# Lab-3NANDx8.net
KiCad netlist of a schematic drawn in EAGLE
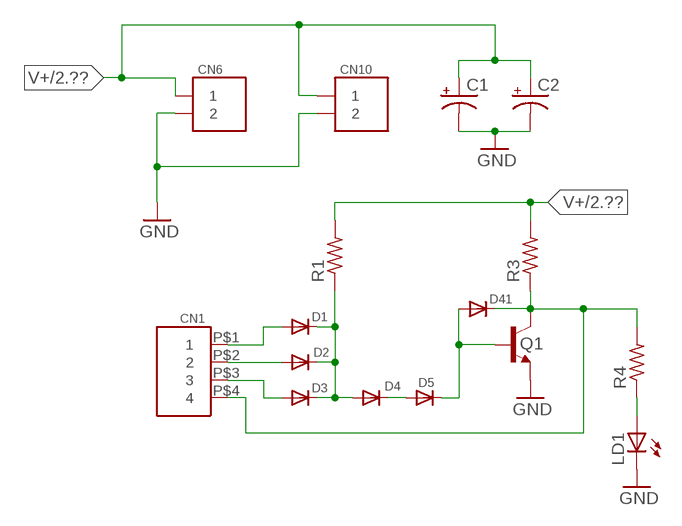
[diagram p0: schematic, sheet 1]
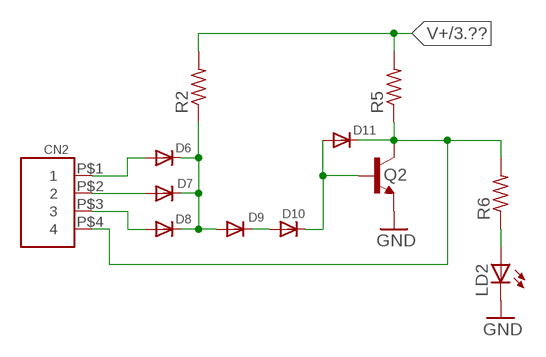
[diagram p1: schematic, sheet 2]
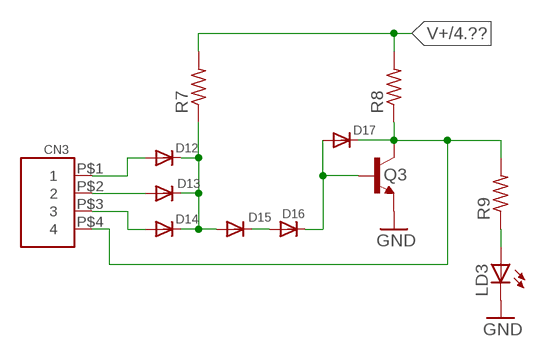
[diagram p2: schematic, sheet 3]
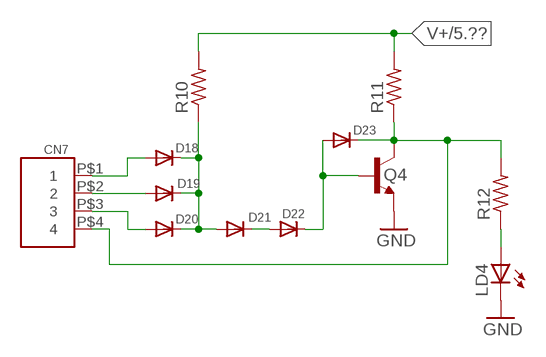
[diagram p3: schematic, sheet 4]
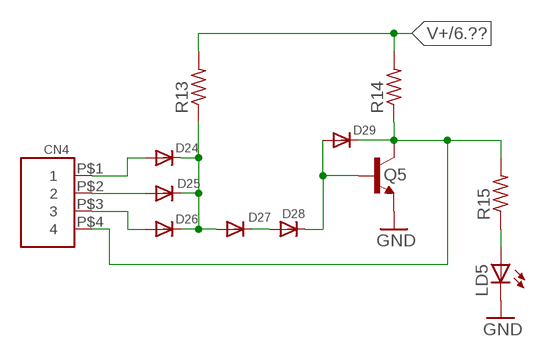
[diagram p4: schematic, sheet 5]
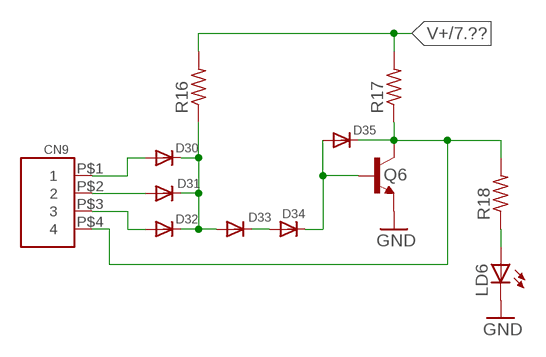
[diagram p5: schematic, sheet 6]
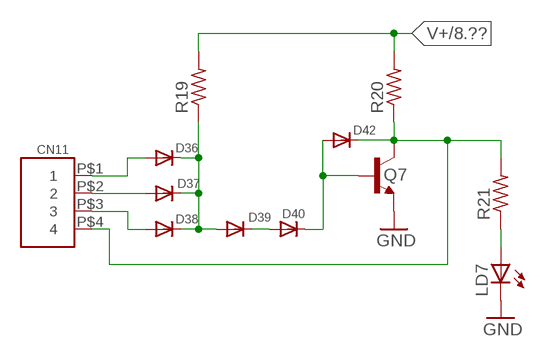
[diagram p6: schematic, sheet 7]
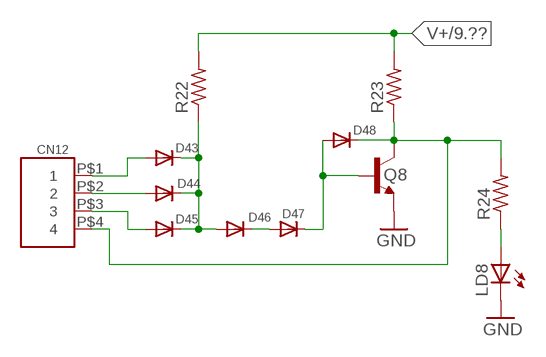
[diagram p7: schematic, sheet 8]
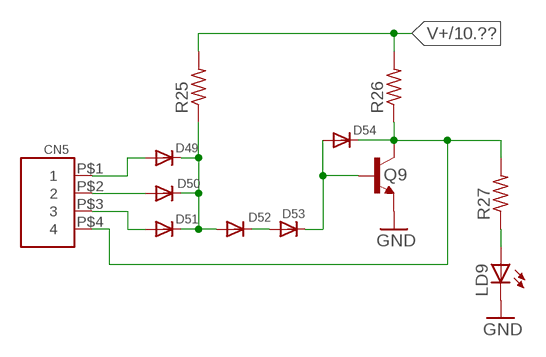
[diagram p8: schematic, sheet 9]
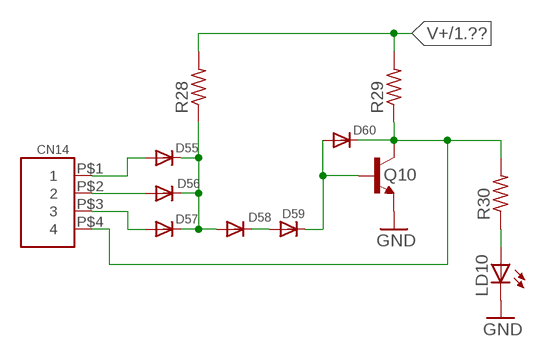
[diagram p9: schematic, sheet 10]

(export (version "E")
  (design (tool "Eeschema 10.0.6"))
  (components
    (comp (ref "CN5")
      (value "HD4")
      (footprint "eagle-import:HD4")
      (libsource (lib "eagle-import") (part "HD4"))
    )
    (comp (ref "D49")
      (value "DIODE-6.3")
      (footprint "eagle-import:DO35-6.3")
      (libsource (lib "eagle-import") (part "DIODE-6.3"))
    )
    (comp (ref "D50")
      (value "DIODE-6.3")
      (footprint "eagle-import:DO35-6.3")
      (libsource (lib "eagle-import") (part "DIODE-6.3"))
    )
    (comp (ref "D51")
      (value "DIODE-6.3")
      (footprint "eagle-import:DO35-6.3")
      (libsource (lib "eagle-import") (part "DIODE-6.3"))
    )
    (comp (ref "D52")
      (value "DIODE-6.3")
      (footprint "eagle-import:DO35-6.3")
      (libsource (lib "eagle-import") (part "DIODE-6.3"))
    )
    (comp (ref "D53")
      (value "DIODE-6.3")
      (footprint "eagle-import:DO35-6.3")
      (libsource (lib "eagle-import") (part "DIODE-6.3"))
    )
    (comp (ref "D54")
      (value "DIODE-7.6")
      (footprint "eagle-import:DO35-7.6")
      (libsource (lib "eagle-import") (part "DIODE-7.6"))
    )
    (comp (ref "LD9")
      (value "LED3MM")
      (footprint "eagle-import:3MM")
      (libsource (lib "eagle-import") (part "LED3MM"))
    )
    (comp (ref "Q9")
      (value "2N3904-1")
      (footprint "eagle-import:TO92BH")
      (libsource (lib "eagle-import") (part "2N3904-1"))
    )
    (comp (ref "R25")
      (value "R1/8-7.6MM")
      (footprint "eagle-import:R0125-7.6")
      (libsource (lib "eagle-import") (part "R1/8-7.6MM"))
    )
    (comp (ref "R26")
      (value "R1/8-7.6MM")
      (footprint "eagle-import:R0125-7.6")
      (libsource (lib "eagle-import") (part "R1/8-7.6MM"))
    )
    (comp (ref "R27")
      (value "R1/8-7.6MM")
      (footprint "eagle-import:R0125-7.6")
      (libsource (lib "eagle-import") (part "R1/8-7.6MM"))
    )
    (comp (ref "CN3")
      (value "HD4")
      (footprint "eagle-import:HD4")
      (libsource (lib "eagle-import") (part "HD4"))
    )
    (comp (ref "D12")
      (value "DIODE-6.3")
      (footprint "eagle-import:DO35-6.3")
      (libsource (lib "eagle-import") (part "DIODE-6.3"))
    )
    (comp (ref "D13")
      (value "DIODE-6.3")
      (footprint "eagle-import:DO35-6.3")
      (libsource (lib "eagle-import") (part "DIODE-6.3"))
    )
    (comp (ref "D14")
      (value "DIODE-6.3")
      (footprint "eagle-import:DO35-6.3")
      (libsource (lib "eagle-import") (part "DIODE-6.3"))
    )
    (comp (ref "D15")
      (value "DIODE-6.3")
      (footprint "eagle-import:DO35-6.3")
      (libsource (lib "eagle-import") (part "DIODE-6.3"))
    )
    (comp (ref "D16")
      (value "DIODE-6.3")
      (footprint "eagle-import:DO35-6.3")
      (libsource (lib "eagle-import") (part "DIODE-6.3"))
    )
    (comp (ref "D17")
      (value "DIODE-7.6")
      (footprint "eagle-import:DO35-7.6")
      (libsource (lib "eagle-import") (part "DIODE-7.6"))
    )
    (comp (ref "LD3")
      (value "LED3MM")
      (footprint "eagle-import:3MM")
      (libsource (lib "eagle-import") (part "LED3MM"))
    )
    (comp (ref "Q3")
      (value "2N3904-1")
      (footprint "eagle-import:TO92BH")
      (libsource (lib "eagle-import") (part "2N3904-1"))
    )
    (comp (ref "R7")
      (value "R1/8-7.6MM")
      (footprint "eagle-import:R0125-7.6")
      (libsource (lib "eagle-import") (part "R1/8-7.6MM"))
    )
    (comp (ref "R8")
      (value "R1/8-7.6MM")
      (footprint "eagle-import:R0125-7.6")
      (libsource (lib "eagle-import") (part "R1/8-7.6MM"))
    )
    (comp (ref "R9")
      (value "R1/8-7.6MM")
      (footprint "eagle-import:R0125-7.6")
      (libsource (lib "eagle-import") (part "R1/8-7.6MM"))
    )
    (comp (ref "C1")
      (value "CPOL-USE2.5-5")
      (footprint "eagle-import:E2,5-5")
      (libsource (lib "eagle-import") (part "CPOL-USE2.5-5"))
    )
    (comp (ref "C2")
      (value "CPOL-USE2.5-5")
      (footprint "eagle-import:E2,5-5")
      (libsource (lib "eagle-import") (part "CPOL-USE2.5-5"))
    )
    (comp (ref "CN1")
      (value "HD4")
      (footprint "eagle-import:HD4")
      (libsource (lib "eagle-import") (part "HD4"))
    )
    (comp (ref "CN6")
      (value "HD2")
      (footprint "eagle-import:HD2")
      (libsource (lib "eagle-import") (part "HD2"))
    )
    (comp (ref "CN10")
      (value "HD2")
      (footprint "eagle-import:HD2")
      (libsource (lib "eagle-import") (part "HD2"))
    )
    (comp (ref "D1")
      (value "DIODE-6.3")
      (footprint "eagle-import:DO35-6.3")
      (libsource (lib "eagle-import") (part "DIODE-6.3"))
    )
    (comp (ref "D2")
      (value "DIODE-6.3")
      (footprint "eagle-import:DO35-6.3")
      (libsource (lib "eagle-import") (part "DIODE-6.3"))
    )
    (comp (ref "D3")
      (value "DIODE-6.3")
      (footprint "eagle-import:DO35-6.3")
      (libsource (lib "eagle-import") (part "DIODE-6.3"))
    )
    (comp (ref "D4")
      (value "DIODE-6.3")
      (footprint "eagle-import:DO35-6.3")
      (libsource (lib "eagle-import") (part "DIODE-6.3"))
    )
    (comp (ref "D5")
      (value "DIODE-6.3")
      (footprint "eagle-import:DO35-6.3")
      (libsource (lib "eagle-import") (part "DIODE-6.3"))
    )
    (comp (ref "D41")
      (value "DIODE-7.6")
      (footprint "eagle-import:DO35-7.6")
      (libsource (lib "eagle-import") (part "DIODE-7.6"))
    )
    (comp (ref "LD1")
      (value "LED3MM")
      (footprint "eagle-import:3MM")
      (libsource (lib "eagle-import") (part "LED3MM"))
    )
    (comp (ref "Q1")
      (value "2N3904-1")
      (footprint "eagle-import:TO92BH")
      (libsource (lib "eagle-import") (part "2N3904-1"))
    )
    (comp (ref "R1")
      (value "R1/8-7.6MM")
      (footprint "eagle-import:R0125-7.6")
      (libsource (lib "eagle-import") (part "R1/8-7.6MM"))
    )
    (comp (ref "R3")
      (value "R1/8-7.6MM")
      (footprint "eagle-import:R0125-7.6")
      (libsource (lib "eagle-import") (part "R1/8-7.6MM"))
    )
    (comp (ref "R4")
      (value "R1/8-7.6MM")
      (footprint "eagle-import:R0125-7.6")
      (libsource (lib "eagle-import") (part "R1/8-7.6MM"))
    )
    (comp (ref "CN7")
      (value "HD4")
      (footprint "eagle-import:HD4")
      (libsource (lib "eagle-import") (part "HD4"))
    )
    (comp (ref "D18")
      (value "DIODE-6.3")
      (footprint "eagle-import:DO35-6.3")
      (libsource (lib "eagle-import") (part "DIODE-6.3"))
    )
    (comp (ref "D19")
      (value "DIODE-6.3")
      (footprint "eagle-import:DO35-6.3")
      (libsource (lib "eagle-import") (part "DIODE-6.3"))
    )
    (comp (ref "D20")
      (value "DIODE-6.3")
      (footprint "eagle-import:DO35-6.3")
      (libsource (lib "eagle-import") (part "DIODE-6.3"))
    )
    (comp (ref "D21")
      (value "DIODE-6.3")
      (footprint "eagle-import:DO35-6.3")
      (libsource (lib "eagle-import") (part "DIODE-6.3"))
    )
    (comp (ref "D22")
      (value "DIODE-6.3")
      (footprint "eagle-import:DO35-6.3")
      (libsource (lib "eagle-import") (part "DIODE-6.3"))
    )
    (comp (ref "D23")
      (value "DIODE-7.6")
      (footprint "eagle-import:DO35-7.6")
      (libsource (lib "eagle-import") (part "DIODE-7.6"))
    )
    (comp (ref "LD4")
      (value "LED3MM")
      (footprint "eagle-import:3MM")
      (libsource (lib "eagle-import") (part "LED3MM"))
    )
    (comp (ref "Q4")
      (value "2N3904-1")
      (footprint "eagle-import:TO92BH")
      (libsource (lib "eagle-import") (part "2N3904-1"))
    )
    (comp (ref "R10")
      (value "R1/8-7.6MM")
      (footprint "eagle-import:R0125-7.6")
      (libsource (lib "eagle-import") (part "R1/8-7.6MM"))
    )
    (comp (ref "R11")
      (value "R1/8-7.6MM")
      (footprint "eagle-import:R0125-7.6")
      (libsource (lib "eagle-import") (part "R1/8-7.6MM"))
    )
    (comp (ref "R12")
      (value "R1/8-7.6MM")
      (footprint "eagle-import:R0125-7.6")
      (libsource (lib "eagle-import") (part "R1/8-7.6MM"))
    )
    (comp (ref "CN2")
      (value "HD4")
      (footprint "eagle-import:HD4")
      (libsource (lib "eagle-import") (part "HD4"))
    )
    (comp (ref "D6")
      (value "DIODE-6.3")
      (footprint "eagle-import:DO35-6.3")
      (libsource (lib "eagle-import") (part "DIODE-6.3"))
    )
    (comp (ref "D7")
      (value "DIODE-6.3")
      (footprint "eagle-import:DO35-6.3")
      (libsource (lib "eagle-import") (part "DIODE-6.3"))
    )
    (comp (ref "D8")
      (value "DIODE-6.3")
      (footprint "eagle-import:DO35-6.3")
      (libsource (lib "eagle-import") (part "DIODE-6.3"))
    )
    (comp (ref "D9")
      (value "DIODE-6.3")
      (footprint "eagle-import:DO35-6.3")
      (libsource (lib "eagle-import") (part "DIODE-6.3"))
    )
    (comp (ref "D10")
      (value "DIODE-6.3")
      (footprint "eagle-import:DO35-6.3")
      (libsource (lib "eagle-import") (part "DIODE-6.3"))
    )
    (comp (ref "D11")
      (value "DIODE-7.6")
      (footprint "eagle-import:DO35-7.6")
      (libsource (lib "eagle-import") (part "DIODE-7.6"))
    )
    (comp (ref "LD2")
      (value "LED3MM")
      (footprint "eagle-import:3MM")
      (libsource (lib "eagle-import") (part "LED3MM"))
    )
    (comp (ref "Q2")
      (value "2N3904-1")
      (footprint "eagle-import:TO92BH")
      (libsource (lib "eagle-import") (part "2N3904-1"))
    )
    (comp (ref "R2")
      (value "R1/8-7.6MM")
      (footprint "eagle-import:R0125-7.6")
      (libsource (lib "eagle-import") (part "R1/8-7.6MM"))
    )
    (comp (ref "R5")
      (value "R1/8-7.6MM")
      (footprint "eagle-import:R0125-7.6")
      (libsource (lib "eagle-import") (part "R1/8-7.6MM"))
    )
    (comp (ref "R6")
      (value "R1/8-7.6MM")
      (footprint "eagle-import:R0125-7.6")
      (libsource (lib "eagle-import") (part "R1/8-7.6MM"))
    )
    (comp (ref "CN9")
      (value "HD4")
      (footprint "eagle-import:HD4")
      (libsource (lib "eagle-import") (part "HD4"))
    )
    (comp (ref "D30")
      (value "DIODE-6.3")
      (footprint "eagle-import:DO35-6.3")
      (libsource (lib "eagle-import") (part "DIODE-6.3"))
    )
    (comp (ref "D31")
      (value "DIODE-6.3")
      (footprint "eagle-import:DO35-6.3")
      (libsource (lib "eagle-import") (part "DIODE-6.3"))
    )
    (comp (ref "D32")
      (value "DIODE-6.3")
      (footprint "eagle-import:DO35-6.3")
      (libsource (lib "eagle-import") (part "DIODE-6.3"))
    )
    (comp (ref "D33")
      (value "DIODE-6.3")
      (footprint "eagle-import:DO35-6.3")
      (libsource (lib "eagle-import") (part "DIODE-6.3"))
    )
    (comp (ref "D34")
      (value "DIODE-6.3")
      (footprint "eagle-import:DO35-6.3")
      (libsource (lib "eagle-import") (part "DIODE-6.3"))
    )
    (comp (ref "D35")
      (value "DIODE-7.6")
      (footprint "eagle-import:DO35-7.6")
      (libsource (lib "eagle-import") (part "DIODE-7.6"))
    )
    (comp (ref "LD6")
      (value "LED3MM")
      (footprint "eagle-import:3MM")
      (libsource (lib "eagle-import") (part "LED3MM"))
    )
    (comp (ref "Q6")
      (value "2N3904-1")
      (footprint "eagle-import:TO92BH")
      (libsource (lib "eagle-import") (part "2N3904-1"))
    )
    (comp (ref "R16")
      (value "R1/8-7.6MM")
      (footprint "eagle-import:R0125-7.6")
      (libsource (lib "eagle-import") (part "R1/8-7.6MM"))
    )
    (comp (ref "R17")
      (value "R1/8-7.6MM")
      (footprint "eagle-import:R0125-7.6")
      (libsource (lib "eagle-import") (part "R1/8-7.6MM"))
    )
    (comp (ref "R18")
      (value "R1/8-7.6MM")
      (footprint "eagle-import:R0125-7.6")
      (libsource (lib "eagle-import") (part "R1/8-7.6MM"))
    )
    (comp (ref "CN4")
      (value "HD4")
      (footprint "eagle-import:HD4")
      (libsource (lib "eagle-import") (part "HD4"))
    )
    (comp (ref "D24")
      (value "DIODE-6.3")
      (footprint "eagle-import:DO35-6.3")
      (libsource (lib "eagle-import") (part "DIODE-6.3"))
    )
    (comp (ref "D25")
      (value "DIODE-6.3")
      (footprint "eagle-import:DO35-6.3")
      (libsource (lib "eagle-import") (part "DIODE-6.3"))
    )
    (comp (ref "D26")
      (value "DIODE-6.3")
      (footprint "eagle-import:DO35-6.3")
      (libsource (lib "eagle-import") (part "DIODE-6.3"))
    )
    (comp (ref "D27")
      (value "DIODE-6.3")
      (footprint "eagle-import:DO35-6.3")
      (libsource (lib "eagle-import") (part "DIODE-6.3"))
    )
    (comp (ref "D28")
      (value "DIODE-6.3")
      (footprint "eagle-import:DO35-6.3")
      (libsource (lib "eagle-import") (part "DIODE-6.3"))
    )
    (comp (ref "D29")
      (value "DIODE-7.6")
      (footprint "eagle-import:DO35-7.6")
      (libsource (lib "eagle-import") (part "DIODE-7.6"))
    )
    (comp (ref "LD5")
      (value "LED3MM")
      (footprint "eagle-import:3MM")
      (libsource (lib "eagle-import") (part "LED3MM"))
    )
    (comp (ref "Q5")
      (value "2N3904-1")
      (footprint "eagle-import:TO92BH")
      (libsource (lib "eagle-import") (part "2N3904-1"))
    )
    (comp (ref "R13")
      (value "R1/8-7.6MM")
      (footprint "eagle-import:R0125-7.6")
      (libsource (lib "eagle-import") (part "R1/8-7.6MM"))
    )
    (comp (ref "R14")
      (value "R1/8-7.6MM")
      (footprint "eagle-import:R0125-7.6")
      (libsource (lib "eagle-import") (part "R1/8-7.6MM"))
    )
    (comp (ref "R15")
      (value "R1/8-7.6MM")
      (footprint "eagle-import:R0125-7.6")
      (libsource (lib "eagle-import") (part "R1/8-7.6MM"))
    )
    (comp (ref "CN12")
      (value "HD4")
      (footprint "eagle-import:HD4")
      (libsource (lib "eagle-import") (part "HD4"))
    )
    (comp (ref "D43")
      (value "DIODE-6.3")
      (footprint "eagle-import:DO35-6.3")
      (libsource (lib "eagle-import") (part "DIODE-6.3"))
    )
    (comp (ref "D44")
      (value "DIODE-6.3")
      (footprint "eagle-import:DO35-6.3")
      (libsource (lib "eagle-import") (part "DIODE-6.3"))
    )
    (comp (ref "D45")
      (value "DIODE-6.3")
      (footprint "eagle-import:DO35-6.3")
      (libsource (lib "eagle-import") (part "DIODE-6.3"))
    )
    (comp (ref "D46")
      (value "DIODE-6.3")
      (footprint "eagle-import:DO35-6.3")
      (libsource (lib "eagle-import") (part "DIODE-6.3"))
    )
    (comp (ref "D47")
      (value "DIODE-6.3")
      (footprint "eagle-import:DO35-6.3")
      (libsource (lib "eagle-import") (part "DIODE-6.3"))
    )
    (comp (ref "D48")
      (value "DIODE-7.6")
      (footprint "eagle-import:DO35-7.6")
      (libsource (lib "eagle-import") (part "DIODE-7.6"))
    )
    (comp (ref "LD8")
      (value "LED3MM")
      (footprint "eagle-import:3MM")
      (libsource (lib "eagle-import") (part "LED3MM"))
    )
    (comp (ref "Q8")
      (value "2N3904-1")
      (footprint "eagle-import:TO92BH")
      (libsource (lib "eagle-import") (part "2N3904-1"))
    )
    (comp (ref "R22")
      (value "R1/8-7.6MM")
      (footprint "eagle-import:R0125-7.6")
      (libsource (lib "eagle-import") (part "R1/8-7.6MM"))
    )
    (comp (ref "R23")
      (value "R1/8-7.6MM")
      (footprint "eagle-import:R0125-7.6")
      (libsource (lib "eagle-import") (part "R1/8-7.6MM"))
    )
    (comp (ref "R24")
      (value "R1/8-7.6MM")
      (footprint "eagle-import:R0125-7.6")
      (libsource (lib "eagle-import") (part "R1/8-7.6MM"))
    )
    (comp (ref "CN11")
      (value "HD4")
      (footprint "eagle-import:HD4")
      (libsource (lib "eagle-import") (part "HD4"))
    )
    (comp (ref "D36")
      (value "DIODE-6.3")
      (footprint "eagle-import:DO35-6.3")
      (libsource (lib "eagle-import") (part "DIODE-6.3"))
    )
    (comp (ref "D37")
      (value "DIODE-6.3")
      (footprint "eagle-import:DO35-6.3")
      (libsource (lib "eagle-import") (part "DIODE-6.3"))
    )
    (comp (ref "D38")
      (value "DIODE-6.3")
      (footprint "eagle-import:DO35-6.3")
      (libsource (lib "eagle-import") (part "DIODE-6.3"))
    )
    (comp (ref "D39")
      (value "DIODE-6.3")
      (footprint "eagle-import:DO35-6.3")
      (libsource (lib "eagle-import") (part "DIODE-6.3"))
    )
    (comp (ref "D40")
      (value "DIODE-6.3")
      (footprint "eagle-import:DO35-6.3")
      (libsource (lib "eagle-import") (part "DIODE-6.3"))
    )
    (comp (ref "D42")
      (value "DIODE-7.6")
      (footprint "eagle-import:DO35-7.6")
      (libsource (lib "eagle-import") (part "DIODE-7.6"))
    )
    (comp (ref "LD7")
      (value "LED3MM")
      (footprint "eagle-import:3MM")
      (libsource (lib "eagle-import") (part "LED3MM"))
    )
    (comp (ref "Q7")
      (value "2N3904-1")
      (footprint "eagle-import:TO92BH")
      (libsource (lib "eagle-import") (part "2N3904-1"))
    )
    (comp (ref "R19")
      (value "R1/8-7.6MM")
      (footprint "eagle-import:R0125-7.6")
      (libsource (lib "eagle-import") (part "R1/8-7.6MM"))
    )
    (comp (ref "R20")
      (value "R1/8-7.6MM")
      (footprint "eagle-import:R0125-7.6")
      (libsource (lib "eagle-import") (part "R1/8-7.6MM"))
    )
    (comp (ref "R21")
      (value "R1/8-7.6MM")
      (footprint "eagle-import:R0125-7.6")
      (libsource (lib "eagle-import") (part "R1/8-7.6MM"))
    )
    (comp (ref "CN14")
      (value "HD4")
      (footprint "eagle-import:HD4")
      (libsource (lib "eagle-import") (part "HD4"))
    )
    (comp (ref "D55")
      (value "DIODE-6.3")
      (footprint "eagle-import:DO35-6.3")
      (libsource (lib "eagle-import") (part "DIODE-6.3"))
    )
    (comp (ref "D56")
      (value "DIODE-6.3")
      (footprint "eagle-import:DO35-6.3")
      (libsource (lib "eagle-import") (part "DIODE-6.3"))
    )
    (comp (ref "D57")
      (value "DIODE-6.3")
      (footprint "eagle-import:DO35-6.3")
      (libsource (lib "eagle-import") (part "DIODE-6.3"))
    )
    (comp (ref "D58")
      (value "DIODE-6.3")
      (footprint "eagle-import:DO35-6.3")
      (libsource (lib "eagle-import") (part "DIODE-6.3"))
    )
    (comp (ref "D59")
      (value "DIODE-6.3")
      (footprint "eagle-import:DO35-6.3")
      (libsource (lib "eagle-import") (part "DIODE-6.3"))
    )
    (comp (ref "D60")
      (value "DIODE-7.6")
      (footprint "eagle-import:DO35-7.6")
      (libsource (lib "eagle-import") (part "DIODE-7.6"))
    )
    (comp (ref "LD10")
      (value "LED3MM")
      (footprint "eagle-import:3MM")
      (libsource (lib "eagle-import") (part "LED3MM"))
    )
    (comp (ref "Q10")
      (value "2N3904-1")
      (footprint "eagle-import:TO92BH")
      (libsource (lib "eagle-import") (part "2N3904-1"))
    )
    (comp (ref "R28")
      (value "R1/8-7.6MM")
      (footprint "eagle-import:R0125-7.6")
      (libsource (lib "eagle-import") (part "R1/8-7.6MM"))
    )
    (comp (ref "R29")
      (value "R1/8-7.6MM")
      (footprint "eagle-import:R0125-7.6")
      (libsource (lib "eagle-import") (part "R1/8-7.6MM"))
    )
    (comp (ref "R30")
      (value "R1/8-7.6MM")
      (footprint "eagle-import:R0125-7.6")
      (libsource (lib "eagle-import") (part "R1/8-7.6MM"))
    )
  )
  (nets
    (net (code "1") (name "GND") (class "Default")
      (node (ref "C1") (pin "-") (pinfunction "-_-") (pintype "passive"))
      (node (ref "C2") (pin "-") (pinfunction "-_-") (pintype "passive"))
      (node (ref "CN10") (pin "P$2") (pinfunction "2_P$2") (pintype "bidirectional"))
      (node (ref "CN6") (pin "P$2") (pinfunction "2_P$2") (pintype "bidirectional"))
      (node (ref "LD1") (pin "C") (pinfunction "C_C") (pintype "bidirectional"))
      (node (ref "LD10") (pin "C") (pinfunction "C_C") (pintype "bidirectional"))
      (node (ref "LD2") (pin "C") (pinfunction "C_C") (pintype "bidirectional"))
      (node (ref "LD3") (pin "C") (pinfunction "C_C") (pintype "bidirectional"))
      (node (ref "LD4") (pin "C") (pinfunction "C_C") (pintype "bidirectional"))
      (node (ref "LD5") (pin "C") (pinfunction "C_C") (pintype "bidirectional"))
      (node (ref "LD6") (pin "C") (pinfunction "C_C") (pintype "bidirectional"))
      (node (ref "LD7") (pin "C") (pinfunction "C_C") (pintype "bidirectional"))
      (node (ref "LD8") (pin "C") (pinfunction "C_C") (pintype "bidirectional"))
      (node (ref "LD9") (pin "C") (pinfunction "C_C") (pintype "bidirectional"))
      (node (ref "Q1") (pin "1") (pinfunction "E_1") (pintype "passive"))
      (node (ref "Q10") (pin "1") (pinfunction "E_1") (pintype "passive"))
      (node (ref "Q2") (pin "1") (pinfunction "E_1") (pintype "passive"))
      (node (ref "Q3") (pin "1") (pinfunction "E_1") (pintype "passive"))
      (node (ref "Q4") (pin "1") (pinfunction "E_1") (pintype "passive"))
      (node (ref "Q5") (pin "1") (pinfunction "E_1") (pintype "passive"))
      (node (ref "Q6") (pin "1") (pinfunction "E_1") (pintype "passive"))
      (node (ref "Q7") (pin "1") (pinfunction "E_1") (pintype "passive"))
      (node (ref "Q8") (pin "1") (pinfunction "E_1") (pintype "passive"))
      (node (ref "Q9") (pin "1") (pinfunction "E_1") (pintype "passive"))
    )
    (net (code "2") (name "Net-(CN1-1)") (class "Default")
      (node (ref "CN1") (pin "P$1") (pinfunction "1_P$1") (pintype "bidirectional"))
      (node (ref "D1") (pin "A") (pinfunction "A_A") (pintype "passive"))
    )
    (net (code "3") (name "Net-(CN1-2)") (class "Default")
      (node (ref "CN1") (pin "P$2") (pinfunction "2_P$2") (pintype "bidirectional"))
      (node (ref "D2") (pin "A") (pinfunction "A_A") (pintype "passive"))
    )
    (net (code "4") (name "Net-(CN1-3)") (class "Default")
      (node (ref "CN1") (pin "P$3") (pinfunction "3_P$3") (pintype "bidirectional"))
      (node (ref "D3") (pin "A") (pinfunction "A_A") (pintype "passive"))
    )
    (net (code "5") (name "Net-(CN1-4)") (class "Default")
      (node (ref "CN1") (pin "P$4") (pinfunction "4_P$4") (pintype "bidirectional"))
      (node (ref "D41") (pin "C") (pinfunction "C_C") (pintype "passive"))
      (node (ref "Q1") (pin "3") (pinfunction "C_3") (pintype "passive"))
      (node (ref "R3") (pin "1") (pinfunction "1_1") (pintype "passive"))
      (node (ref "R4") (pin "2") (pinfunction "2_2") (pintype "passive"))
    )
    (net (code "6") (name "Net-(CN2-1)") (class "Default")
      (node (ref "CN2") (pin "P$1") (pinfunction "1_P$1") (pintype "bidirectional"))
      (node (ref "D6") (pin "A") (pinfunction "A_A") (pintype "passive"))
    )
    (net (code "7") (name "Net-(CN2-2)") (class "Default")
      (node (ref "CN2") (pin "P$2") (pinfunction "2_P$2") (pintype "bidirectional"))
      (node (ref "D7") (pin "A") (pinfunction "A_A") (pintype "passive"))
    )
    (net (code "8") (name "Net-(CN2-3)") (class "Default")
      (node (ref "CN2") (pin "P$3") (pinfunction "3_P$3") (pintype "bidirectional"))
      (node (ref "D8") (pin "A") (pinfunction "A_A") (pintype "passive"))
    )
    (net (code "9") (name "Net-(CN2-4)") (class "Default")
      (node (ref "CN2") (pin "P$4") (pinfunction "4_P$4") (pintype "bidirectional"))
      (node (ref "D11") (pin "C") (pinfunction "C_C") (pintype "passive"))
      (node (ref "Q2") (pin "3") (pinfunction "C_3") (pintype "passive"))
      (node (ref "R5") (pin "1") (pinfunction "1_1") (pintype "passive"))
      (node (ref "R6") (pin "2") (pinfunction "2_2") (pintype "passive"))
    )
    (net (code "10") (name "Net-(CN3-1)") (class "Default")
      (node (ref "CN3") (pin "P$1") (pinfunction "1_P$1") (pintype "bidirectional"))
      (node (ref "D12") (pin "A") (pinfunction "A_A") (pintype "passive"))
    )
    (net (code "11") (name "Net-(CN3-2)") (class "Default")
      (node (ref "CN3") (pin "P$2") (pinfunction "2_P$2") (pintype "bidirectional"))
      (node (ref "D13") (pin "A") (pinfunction "A_A") (pintype "passive"))
    )
    (net (code "12") (name "Net-(CN3-3)") (class "Default")
      (node (ref "CN3") (pin "P$3") (pinfunction "3_P$3") (pintype "bidirectional"))
      (node (ref "D14") (pin "A") (pinfunction "A_A") (pintype "passive"))
    )
    (net (code "13") (name "Net-(CN3-4)") (class "Default")
      (node (ref "CN3") (pin "P$4") (pinfunction "4_P$4") (pintype "bidirectional"))
      (node (ref "D17") (pin "C") (pinfunction "C_C") (pintype "passive"))
      (node (ref "Q3") (pin "3") (pinfunction "C_3") (pintype "passive"))
      (node (ref "R8") (pin "1") (pinfunction "1_1") (pintype "passive"))
      (node (ref "R9") (pin "2") (pinfunction "2_2") (pintype "passive"))
    )
    (net (code "14") (name "Net-(CN4-1)") (class "Default")
      (node (ref "CN4") (pin "P$1") (pinfunction "1_P$1") (pintype "bidirectional"))
      (node (ref "D24") (pin "A") (pinfunction "A_A") (pintype "passive"))
    )
    (net (code "15") (name "Net-(CN4-2)") (class "Default")
      (node (ref "CN4") (pin "P$2") (pinfunction "2_P$2") (pintype "bidirectional"))
      (node (ref "D25") (pin "A") (pinfunction "A_A") (pintype "passive"))
    )
    (net (code "16") (name "Net-(CN4-3)") (class "Default")
      (node (ref "CN4") (pin "P$3") (pinfunction "3_P$3") (pintype "bidirectional"))
      (node (ref "D26") (pin "A") (pinfunction "A_A") (pintype "passive"))
    )
    (net (code "17") (name "Net-(CN4-4)") (class "Default")
      (node (ref "CN4") (pin "P$4") (pinfunction "4_P$4") (pintype "bidirectional"))
      (node (ref "D29") (pin "C") (pinfunction "C_C") (pintype "passive"))
      (node (ref "Q5") (pin "3") (pinfunction "C_3") (pintype "passive"))
      (node (ref "R14") (pin "1") (pinfunction "1_1") (pintype "passive"))
      (node (ref "R15") (pin "2") (pinfunction "2_2") (pintype "passive"))
    )
    (net (code "18") (name "Net-(CN5-1)") (class "Default")
      (node (ref "CN5") (pin "P$1") (pinfunction "1_P$1") (pintype "bidirectional"))
      (node (ref "D49") (pin "A") (pinfunction "A_A") (pintype "passive"))
    )
    (net (code "19") (name "Net-(CN5-2)") (class "Default")
      (node (ref "CN5") (pin "P$2") (pinfunction "2_P$2") (pintype "bidirectional"))
      (node (ref "D50") (pin "A") (pinfunction "A_A") (pintype "passive"))
    )
    (net (code "20") (name "Net-(CN5-3)") (class "Default")
      (node (ref "CN5") (pin "P$3") (pinfunction "3_P$3") (pintype "bidirectional"))
      (node (ref "D51") (pin "A") (pinfunction "A_A") (pintype "passive"))
    )
    (net (code "21") (name "Net-(CN5-4)") (class "Default")
      (node (ref "CN5") (pin "P$4") (pinfunction "4_P$4") (pintype "bidirectional"))
      (node (ref "D54") (pin "C") (pinfunction "C_C") (pintype "passive"))
      (node (ref "Q9") (pin "3") (pinfunction "C_3") (pintype "passive"))
      (node (ref "R26") (pin "1") (pinfunction "1_1") (pintype "passive"))
      (node (ref "R27") (pin "2") (pinfunction "2_2") (pintype "passive"))
    )
    (net (code "22") (name "Net-(CN7-1)") (class "Default")
      (node (ref "CN7") (pin "P$1") (pinfunction "1_P$1") (pintype "bidirectional"))
      (node (ref "D18") (pin "A") (pinfunction "A_A") (pintype "passive"))
    )
    (net (code "23") (name "Net-(CN7-2)") (class "Default")
      (node (ref "CN7") (pin "P$2") (pinfunction "2_P$2") (pintype "bidirectional"))
      (node (ref "D19") (pin "A") (pinfunction "A_A") (pintype "passive"))
    )
    (net (code "24") (name "Net-(CN7-3)") (class "Default")
      (node (ref "CN7") (pin "P$3") (pinfunction "3_P$3") (pintype "bidirectional"))
      (node (ref "D20") (pin "A") (pinfunction "A_A") (pintype "passive"))
    )
    (net (code "25") (name "Net-(CN7-4)") (class "Default")
      (node (ref "CN7") (pin "P$4") (pinfunction "4_P$4") (pintype "bidirectional"))
      (node (ref "D23") (pin "C") (pinfunction "C_C") (pintype "passive"))
      (node (ref "Q4") (pin "3") (pinfunction "C_3") (pintype "passive"))
      (node (ref "R11") (pin "1") (pinfunction "1_1") (pintype "passive"))
      (node (ref "R12") (pin "2") (pinfunction "2_2") (pintype "passive"))
    )
    (net (code "26") (name "Net-(CN9-1)") (class "Default")
      (node (ref "CN9") (pin "P$1") (pinfunction "1_P$1") (pintype "bidirectional"))
      (node (ref "D30") (pin "A") (pinfunction "A_A") (pintype "passive"))
    )
    (net (code "27") (name "Net-(CN9-2)") (class "Default")
      (node (ref "CN9") (pin "P$2") (pinfunction "2_P$2") (pintype "bidirectional"))
      (node (ref "D31") (pin "A") (pinfunction "A_A") (pintype "passive"))
    )
    (net (code "28") (name "Net-(CN9-3)") (class "Default")
      (node (ref "CN9") (pin "P$3") (pinfunction "3_P$3") (pintype "bidirectional"))
      (node (ref "D32") (pin "A") (pinfunction "A_A") (pintype "passive"))
    )
    (net (code "29") (name "Net-(CN9-4)") (class "Default")
      (node (ref "CN9") (pin "P$4") (pinfunction "4_P$4") (pintype "bidirectional"))
      (node (ref "D35") (pin "C") (pinfunction "C_C") (pintype "passive"))
      (node (ref "Q6") (pin "3") (pinfunction "C_3") (pintype "passive"))
      (node (ref "R17") (pin "1") (pinfunction "1_1") (pintype "passive"))
      (node (ref "R18") (pin "2") (pinfunction "2_2") (pintype "passive"))
    )
    (net (code "30") (name "Net-(CN11-1)") (class "Default")
      (node (ref "CN11") (pin "P$1") (pinfunction "1_P$1") (pintype "bidirectional"))
      (node (ref "D36") (pin "A") (pinfunction "A_A") (pintype "passive"))
    )
    (net (code "31") (name "Net-(CN11-2)") (class "Default")
      (node (ref "CN11") (pin "P$2") (pinfunction "2_P$2") (pintype "bidirectional"))
      (node (ref "D37") (pin "A") (pinfunction "A_A") (pintype "passive"))
    )
    (net (code "32") (name "Net-(CN11-3)") (class "Default")
      (node (ref "CN11") (pin "P$3") (pinfunction "3_P$3") (pintype "bidirectional"))
      (node (ref "D38") (pin "A") (pinfunction "A_A") (pintype "passive"))
    )
    (net (code "33") (name "Net-(CN11-4)") (class "Default")
      (node (ref "CN11") (pin "P$4") (pinfunction "4_P$4") (pintype "bidirectional"))
      (node (ref "D42") (pin "C") (pinfunction "C_C") (pintype "passive"))
      (node (ref "Q7") (pin "3") (pinfunction "C_3") (pintype "passive"))
      (node (ref "R20") (pin "1") (pinfunction "1_1") (pintype "passive"))
      (node (ref "R21") (pin "2") (pinfunction "2_2") (pintype "passive"))
    )
    (net (code "34") (name "Net-(CN12-1)") (class "Default")
      (node (ref "CN12") (pin "P$1") (pinfunction "1_P$1") (pintype "bidirectional"))
      (node (ref "D43") (pin "A") (pinfunction "A_A") (pintype "passive"))
    )
    (net (code "35") (name "Net-(CN12-2)") (class "Default")
      (node (ref "CN12") (pin "P$2") (pinfunction "2_P$2") (pintype "bidirectional"))
      (node (ref "D44") (pin "A") (pinfunction "A_A") (pintype "passive"))
    )
    (net (code "36") (name "Net-(CN12-3)") (class "Default")
      (node (ref "CN12") (pin "P$3") (pinfunction "3_P$3") (pintype "bidirectional"))
      (node (ref "D45") (pin "A") (pinfunction "A_A") (pintype "passive"))
    )
    (net (code "37") (name "Net-(CN12-4)") (class "Default")
      (node (ref "CN12") (pin "P$4") (pinfunction "4_P$4") (pintype "bidirectional"))
      (node (ref "D48") (pin "C") (pinfunction "C_C") (pintype "passive"))
      (node (ref "Q8") (pin "3") (pinfunction "C_3") (pintype "passive"))
      (node (ref "R23") (pin "1") (pinfunction "1_1") (pintype "passive"))
      (node (ref "R24") (pin "2") (pinfunction "2_2") (pintype "passive"))
    )
    (net (code "38") (name "Net-(CN14-1)") (class "Default")
      (node (ref "CN14") (pin "P$1") (pinfunction "1_P$1") (pintype "bidirectional"))
      (node (ref "D55") (pin "A") (pinfunction "A_A") (pintype "passive"))
    )
    (net (code "39") (name "Net-(CN14-2)") (class "Default")
      (node (ref "CN14") (pin "P$2") (pinfunction "2_P$2") (pintype "bidirectional"))
      (node (ref "D56") (pin "A") (pinfunction "A_A") (pintype "passive"))
    )
    (net (code "40") (name "Net-(CN14-3)") (class "Default")
      (node (ref "CN14") (pin "P$3") (pinfunction "3_P$3") (pintype "bidirectional"))
      (node (ref "D57") (pin "A") (pinfunction "A_A") (pintype "passive"))
    )
    (net (code "41") (name "Net-(CN14-4)") (class "Default")
      (node (ref "CN14") (pin "P$4") (pinfunction "4_P$4") (pintype "bidirectional"))
      (node (ref "D60") (pin "C") (pinfunction "C_C") (pintype "passive"))
      (node (ref "Q10") (pin "3") (pinfunction "C_3") (pintype "passive"))
      (node (ref "R29") (pin "1") (pinfunction "1_1") (pintype "passive"))
      (node (ref "R30") (pin "2") (pinfunction "2_2") (pintype "passive"))
    )
    (net (code "42") (name "Net-(D1-PadC)") (class "Default")
      (node (ref "D1") (pin "C") (pinfunction "C_C") (pintype "passive"))
      (node (ref "D2") (pin "C") (pinfunction "C_C") (pintype "passive"))
      (node (ref "D3") (pin "C") (pinfunction "C_C") (pintype "passive"))
      (node (ref "D4") (pin "A") (pinfunction "A_A") (pintype "passive"))
      (node (ref "R1") (pin "1") (pinfunction "1_1") (pintype "passive"))
    )
    (net (code "43") (name "Net-(D4-PadC)") (class "Default")
      (node (ref "D4") (pin "C") (pinfunction "C_C") (pintype "passive"))
      (node (ref "D5") (pin "A") (pinfunction "A_A") (pintype "passive"))
    )
    (net (code "44") (name "Net-(D6-PadC)") (class "Default")
      (node (ref "D6") (pin "C") (pinfunction "C_C") (pintype "passive"))
      (node (ref "D7") (pin "C") (pinfunction "C_C") (pintype "passive"))
      (node (ref "D8") (pin "C") (pinfunction "C_C") (pintype "passive"))
      (node (ref "D9") (pin "A") (pinfunction "A_A") (pintype "passive"))
      (node (ref "R2") (pin "1") (pinfunction "1_1") (pintype "passive"))
    )
    (net (code "45") (name "Net-(D10-PadA)") (class "Default")
      (node (ref "D10") (pin "A") (pinfunction "A_A") (pintype "passive"))
      (node (ref "D9") (pin "C") (pinfunction "C_C") (pintype "passive"))
    )
    (net (code "46") (name "Net-(D12-PadC)") (class "Default")
      (node (ref "D12") (pin "C") (pinfunction "C_C") (pintype "passive"))
      (node (ref "D13") (pin "C") (pinfunction "C_C") (pintype "passive"))
      (node (ref "D14") (pin "C") (pinfunction "C_C") (pintype "passive"))
      (node (ref "D15") (pin "A") (pinfunction "A_A") (pintype "passive"))
      (node (ref "R7") (pin "1") (pinfunction "1_1") (pintype "passive"))
    )
    (net (code "47") (name "Net-(D15-PadC)") (class "Default")
      (node (ref "D15") (pin "C") (pinfunction "C_C") (pintype "passive"))
      (node (ref "D16") (pin "A") (pinfunction "A_A") (pintype "passive"))
    )
    (net (code "48") (name "Net-(D18-PadC)") (class "Default")
      (node (ref "D18") (pin "C") (pinfunction "C_C") (pintype "passive"))
      (node (ref "D19") (pin "C") (pinfunction "C_C") (pintype "passive"))
      (node (ref "D20") (pin "C") (pinfunction "C_C") (pintype "passive"))
      (node (ref "D21") (pin "A") (pinfunction "A_A") (pintype "passive"))
      (node (ref "R10") (pin "1") (pinfunction "1_1") (pintype "passive"))
    )
    (net (code "49") (name "Net-(D21-PadC)") (class "Default")
      (node (ref "D21") (pin "C") (pinfunction "C_C") (pintype "passive"))
      (node (ref "D22") (pin "A") (pinfunction "A_A") (pintype "passive"))
    )
    (net (code "50") (name "Net-(D24-PadC)") (class "Default")
      (node (ref "D24") (pin "C") (pinfunction "C_C") (pintype "passive"))
      (node (ref "D25") (pin "C") (pinfunction "C_C") (pintype "passive"))
      (node (ref "D26") (pin "C") (pinfunction "C_C") (pintype "passive"))
      (node (ref "D27") (pin "A") (pinfunction "A_A") (pintype "passive"))
      (node (ref "R13") (pin "1") (pinfunction "1_1") (pintype "passive"))
    )
    (net (code "51") (name "Net-(D27-PadC)") (class "Default")
      (node (ref "D27") (pin "C") (pinfunction "C_C") (pintype "passive"))
      (node (ref "D28") (pin "A") (pinfunction "A_A") (pintype "passive"))
    )
    (net (code "52") (name "Net-(D30-PadC)") (class "Default")
      (node (ref "D30") (pin "C") (pinfunction "C_C") (pintype "passive"))
      (node (ref "D31") (pin "C") (pinfunction "C_C") (pintype "passive"))
      (node (ref "D32") (pin "C") (pinfunction "C_C") (pintype "passive"))
      (node (ref "D33") (pin "A") (pinfunction "A_A") (pintype "passive"))
      (node (ref "R16") (pin "1") (pinfunction "1_1") (pintype "passive"))
    )
    (net (code "53") (name "Net-(D33-PadC)") (class "Default")
      (node (ref "D33") (pin "C") (pinfunction "C_C") (pintype "passive"))
      (node (ref "D34") (pin "A") (pinfunction "A_A") (pintype "passive"))
    )
    (net (code "54") (name "Net-(D36-PadC)") (class "Default")
      (node (ref "D36") (pin "C") (pinfunction "C_C") (pintype "passive"))
      (node (ref "D37") (pin "C") (pinfunction "C_C") (pintype "passive"))
      (node (ref "D38") (pin "C") (pinfunction "C_C") (pintype "passive"))
      (node (ref "D39") (pin "A") (pinfunction "A_A") (pintype "passive"))
      (node (ref "R19") (pin "1") (pinfunction "1_1") (pintype "passive"))
    )
    (net (code "55") (name "Net-(D39-PadC)") (class "Default")
      (node (ref "D39") (pin "C") (pinfunction "C_C") (pintype "passive"))
      (node (ref "D40") (pin "A") (pinfunction "A_A") (pintype "passive"))
    )
    (net (code "56") (name "Net-(D43-PadC)") (class "Default")
      (node (ref "D43") (pin "C") (pinfunction "C_C") (pintype "passive"))
      (node (ref "D44") (pin "C") (pinfunction "C_C") (pintype "passive"))
      (node (ref "D45") (pin "C") (pinfunction "C_C") (pintype "passive"))
      (node (ref "D46") (pin "A") (pinfunction "A_A") (pintype "passive"))
      (node (ref "R22") (pin "1") (pinfunction "1_1") (pintype "passive"))
    )
    (net (code "57") (name "Net-(D46-PadC)") (class "Default")
      (node (ref "D46") (pin "C") (pinfunction "C_C") (pintype "passive"))
      (node (ref "D47") (pin "A") (pinfunction "A_A") (pintype "passive"))
    )
    (net (code "58") (name "Net-(D49-PadC)") (class "Default")
      (node (ref "D49") (pin "C") (pinfunction "C_C") (pintype "passive"))
      (node (ref "D50") (pin "C") (pinfunction "C_C") (pintype "passive"))
      (node (ref "D51") (pin "C") (pinfunction "C_C") (pintype "passive"))
      (node (ref "D52") (pin "A") (pinfunction "A_A") (pintype "passive"))
      (node (ref "R25") (pin "1") (pinfunction "1_1") (pintype "passive"))
    )
    (net (code "59") (name "Net-(D52-PadC)") (class "Default")
      (node (ref "D52") (pin "C") (pinfunction "C_C") (pintype "passive"))
      (node (ref "D53") (pin "A") (pinfunction "A_A") (pintype "passive"))
    )
    (net (code "60") (name "Net-(D55-PadC)") (class "Default")
      (node (ref "D55") (pin "C") (pinfunction "C_C") (pintype "passive"))
      (node (ref "D56") (pin "C") (pinfunction "C_C") (pintype "passive"))
      (node (ref "D57") (pin "C") (pinfunction "C_C") (pintype "passive"))
      (node (ref "D58") (pin "A") (pinfunction "A_A") (pintype "passive"))
      (node (ref "R28") (pin "1") (pinfunction "1_1") (pintype "passive"))
    )
    (net (code "61") (name "Net-(D58-PadC)") (class "Default")
      (node (ref "D58") (pin "C") (pinfunction "C_C") (pintype "passive"))
      (node (ref "D59") (pin "A") (pinfunction "A_A") (pintype "passive"))
    )
    (net (code "62") (name "Net-(LD1-PadA)") (class "Default")
      (node (ref "LD1") (pin "A") (pinfunction "A_A") (pintype "bidirectional"))
      (node (ref "R4") (pin "1") (pinfunction "1_1") (pintype "passive"))
    )
    (net (code "63") (name "Net-(LD2-PadA)") (class "Default")
      (node (ref "LD2") (pin "A") (pinfunction "A_A") (pintype "bidirectional"))
      (node (ref "R6") (pin "1") (pinfunction "1_1") (pintype "passive"))
    )
    (net (code "64") (name "Net-(LD3-PadA)") (class "Default")
      (node (ref "LD3") (pin "A") (pinfunction "A_A") (pintype "bidirectional"))
      (node (ref "R9") (pin "1") (pinfunction "1_1") (pintype "passive"))
    )
    (net (code "65") (name "Net-(LD4-PadA)") (class "Default")
      (node (ref "LD4") (pin "A") (pinfunction "A_A") (pintype "bidirectional"))
      (node (ref "R12") (pin "1") (pinfunction "1_1") (pintype "passive"))
    )
    (net (code "66") (name "Net-(LD5-PadA)") (class "Default")
      (node (ref "LD5") (pin "A") (pinfunction "A_A") (pintype "bidirectional"))
      (node (ref "R15") (pin "1") (pinfunction "1_1") (pintype "passive"))
    )
    (net (code "67") (name "Net-(LD6-PadA)") (class "Default")
      (node (ref "LD6") (pin "A") (pinfunction "A_A") (pintype "bidirectional"))
      (node (ref "R18") (pin "1") (pinfunction "1_1") (pintype "passive"))
    )
    (net (code "68") (name "Net-(LD7-PadA)") (class "Default")
      (node (ref "LD7") (pin "A") (pinfunction "A_A") (pintype "bidirectional"))
      (node (ref "R21") (pin "1") (pinfunction "1_1") (pintype "passive"))
    )
    (net (code "69") (name "Net-(LD8-PadA)") (class "Default")
      (node (ref "LD8") (pin "A") (pinfunction "A_A") (pintype "bidirectional"))
      (node (ref "R24") (pin "1") (pinfunction "1_1") (pintype "passive"))
    )
    (net (code "70") (name "Net-(LD9-PadA)") (class "Default")
      (node (ref "LD9") (pin "A") (pinfunction "A_A") (pintype "bidirectional"))
      (node (ref "R27") (pin "1") (pinfunction "1_1") (pintype "passive"))
    )
    (net (code "71") (name "Net-(LD10-PadA)") (class "Default")
      (node (ref "LD10") (pin "A") (pinfunction "A_A") (pintype "bidirectional"))
      (node (ref "R30") (pin "1") (pinfunction "1_1") (pintype "passive"))
    )
    (net (code "72") (name "Net-(Q1-B)") (class "Default")
      (node (ref "D41") (pin "A") (pinfunction "A_A") (pintype "passive"))
      (node (ref "D5") (pin "C") (pinfunction "C_C") (pintype "passive"))
      (node (ref "Q1") (pin "2") (pinfunction "B_2") (pintype "passive"))
    )
    (net (code "73") (name "Net-(Q2-B)") (class "Default")
      (node (ref "D10") (pin "C") (pinfunction "C_C") (pintype "passive"))
      (node (ref "D11") (pin "A") (pinfunction "A_A") (pintype "passive"))
      (node (ref "Q2") (pin "2") (pinfunction "B_2") (pintype "passive"))
    )
    (net (code "74") (name "Net-(Q3-B)") (class "Default")
      (node (ref "D16") (pin "C") (pinfunction "C_C") (pintype "passive"))
      (node (ref "D17") (pin "A") (pinfunction "A_A") (pintype "passive"))
      (node (ref "Q3") (pin "2") (pinfunction "B_2") (pintype "passive"))
    )
    (net (code "75") (name "Net-(Q4-B)") (class "Default")
      (node (ref "D22") (pin "C") (pinfunction "C_C") (pintype "passive"))
      (node (ref "D23") (pin "A") (pinfunction "A_A") (pintype "passive"))
      (node (ref "Q4") (pin "2") (pinfunction "B_2") (pintype "passive"))
    )
    (net (code "76") (name "Net-(Q5-B)") (class "Default")
      (node (ref "D28") (pin "C") (pinfunction "C_C") (pintype "passive"))
      (node (ref "D29") (pin "A") (pinfunction "A_A") (pintype "passive"))
      (node (ref "Q5") (pin "2") (pinfunction "B_2") (pintype "passive"))
    )
    (net (code "77") (name "Net-(Q6-B)") (class "Default")
      (node (ref "D34") (pin "C") (pinfunction "C_C") (pintype "passive"))
      (node (ref "D35") (pin "A") (pinfunction "A_A") (pintype "passive"))
      (node (ref "Q6") (pin "2") (pinfunction "B_2") (pintype "passive"))
    )
    (net (code "78") (name "Net-(Q7-B)") (class "Default")
      (node (ref "D40") (pin "C") (pinfunction "C_C") (pintype "passive"))
      (node (ref "D42") (pin "A") (pinfunction "A_A") (pintype "passive"))
      (node (ref "Q7") (pin "2") (pinfunction "B_2") (pintype "passive"))
    )
    (net (code "79") (name "Net-(Q8-B)") (class "Default")
      (node (ref "D47") (pin "C") (pinfunction "C_C") (pintype "passive"))
      (node (ref "D48") (pin "A") (pinfunction "A_A") (pintype "passive"))
      (node (ref "Q8") (pin "2") (pinfunction "B_2") (pintype "passive"))
    )
    (net (code "80") (name "Net-(Q9-B)") (class "Default")
      (node (ref "D53") (pin "C") (pinfunction "C_C") (pintype "passive"))
      (node (ref "D54") (pin "A") (pinfunction "A_A") (pintype "passive"))
      (node (ref "Q9") (pin "2") (pinfunction "B_2") (pintype "passive"))
    )
    (net (code "81") (name "Net-(Q10-B)") (class "Default")
      (node (ref "D59") (pin "C") (pinfunction "C_C") (pintype "passive"))
      (node (ref "D60") (pin "A") (pinfunction "A_A") (pintype "passive"))
      (node (ref "Q10") (pin "2") (pinfunction "B_2") (pintype "passive"))
    )
    (net (code "82") (name "V+") (class "Default")
      (node (ref "C1") (pin "+") (pinfunction "+_+") (pintype "passive"))
      (node (ref "C2") (pin "+") (pinfunction "+_+") (pintype "passive"))
      (node (ref "CN10") (pin "P$1") (pinfunction "1_P$1") (pintype "bidirectional"))
      (node (ref "CN6") (pin "P$1") (pinfunction "1_P$1") (pintype "bidirectional"))
      (node (ref "R1") (pin "2") (pinfunction "2_2") (pintype "passive"))
      (node (ref "R10") (pin "2") (pinfunction "2_2") (pintype "passive"))
      (node (ref "R11") (pin "2") (pinfunction "2_2") (pintype "passive"))
      (node (ref "R13") (pin "2") (pinfunction "2_2") (pintype "passive"))
      (node (ref "R14") (pin "2") (pinfunction "2_2") (pintype "passive"))
      (node (ref "R16") (pin "2") (pinfunction "2_2") (pintype "passive"))
      (node (ref "R17") (pin "2") (pinfunction "2_2") (pintype "passive"))
      (node (ref "R19") (pin "2") (pinfunction "2_2") (pintype "passive"))
      (node (ref "R2") (pin "2") (pinfunction "2_2") (pintype "passive"))
      (node (ref "R20") (pin "2") (pinfunction "2_2") (pintype "passive"))
      (node (ref "R22") (pin "2") (pinfunction "2_2") (pintype "passive"))
      (node (ref "R23") (pin "2") (pinfunction "2_2") (pintype "passive"))
      (node (ref "R25") (pin "2") (pinfunction "2_2") (pintype "passive"))
      (node (ref "R26") (pin "2") (pinfunction "2_2") (pintype "passive"))
      (node (ref "R28") (pin "2") (pinfunction "2_2") (pintype "passive"))
      (node (ref "R29") (pin "2") (pinfunction "2_2") (pintype "passive"))
      (node (ref "R3") (pin "2") (pinfunction "2_2") (pintype "passive"))
      (node (ref "R5") (pin "2") (pinfunction "2_2") (pintype "passive"))
      (node (ref "R7") (pin "2") (pinfunction "2_2") (pintype "passive"))
      (node (ref "R8") (pin "2") (pinfunction "2_2") (pintype "passive"))
    )
  )
)
